# usb2can.net
KiCad netlist of a schematic drawn in EAGLE
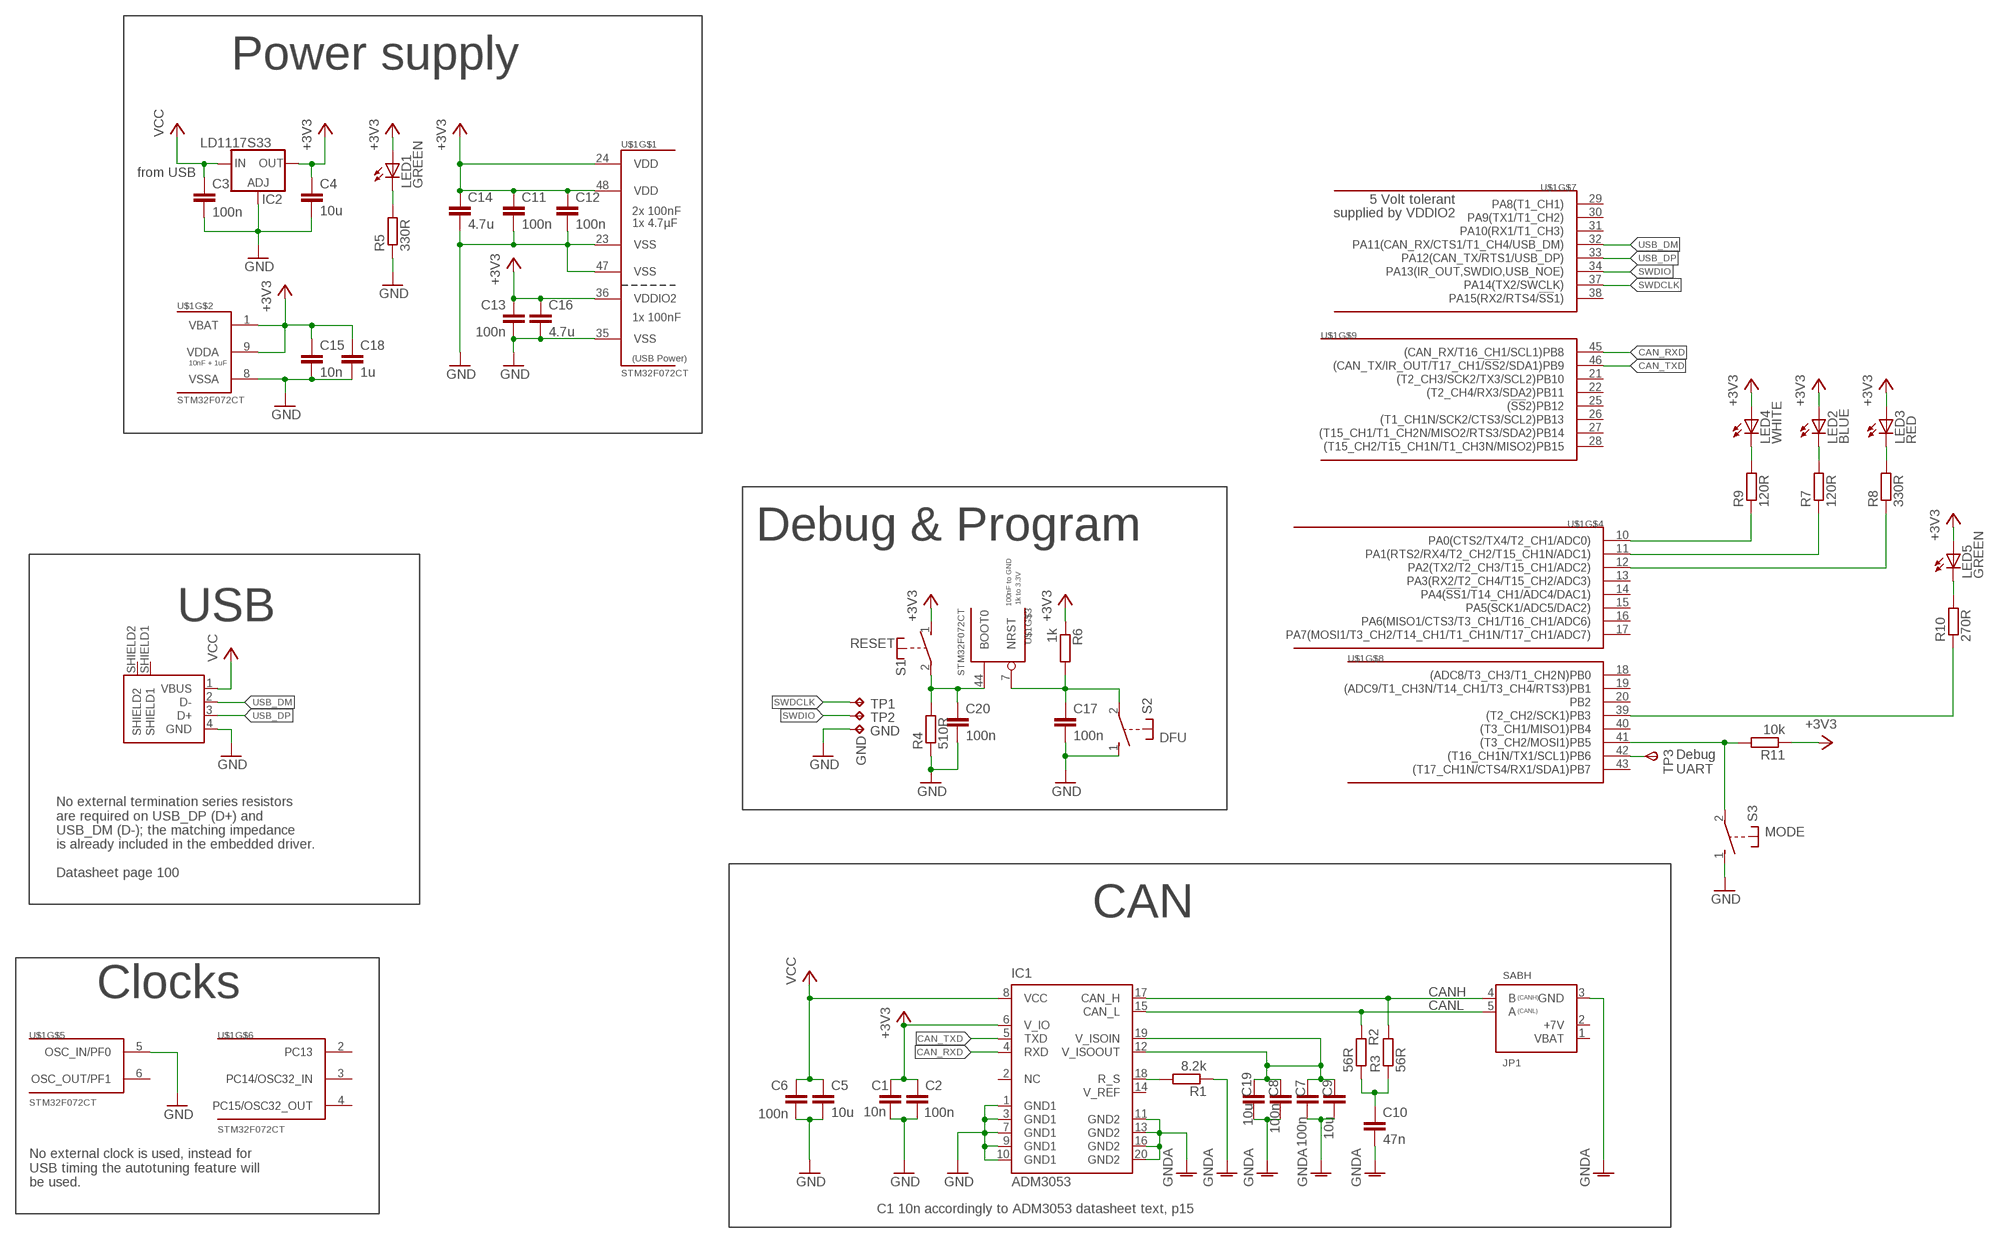
[diagram p0: schematic, sheet 1]

(export (version "E")
  (design (tool "Eeschema 10.0.6"))
  (components
    (comp (ref "C1")
      (value "10n")
      (footprint "eagle-import:C0603K")
      (libsource (lib "eagle-import") (part "C-EUC0603K"))
    )
    (comp (ref "C2")
      (value "100n")
      (footprint "eagle-import:C0603K")
      (libsource (lib "eagle-import") (part "C-EUC0603K"))
    )
    (comp (ref "C3")
      (value "100n")
      (footprint "eagle-import:C0603K")
      (libsource (lib "eagle-import") (part "C-EUC0603K"))
    )
    (comp (ref "C4")
      (value "10u")
      (footprint "eagle-import:C0805K")
      (libsource (lib "eagle-import") (part "C-EUC0805K"))
    )
    (comp (ref "C5")
      (value "10u")
      (footprint "eagle-import:C0805K")
      (libsource (lib "eagle-import") (part "C-EUC0805K"))
    )
    (comp (ref "C6")
      (value "100n")
      (footprint "eagle-import:C0603K")
      (libsource (lib "eagle-import") (part "C-EUC0603K"))
    )
    (comp (ref "C7")
      (value "100n")
      (footprint "eagle-import:C0805K")
      (libsource (lib "eagle-import") (part "C-EUC0805K"))
    )
    (comp (ref "C8")
      (value "100n")
      (footprint "eagle-import:C0805K")
      (libsource (lib "eagle-import") (part "C-EUC0805K"))
    )
    (comp (ref "C9")
      (value "10u")
      (footprint "eagle-import:C0805K")
      (libsource (lib "eagle-import") (part "C-EUC0805K"))
    )
    (comp (ref "C10")
      (value "47n")
      (footprint "eagle-import:C0603K")
      (libsource (lib "eagle-import") (part "C-EUC0603K"))
    )
    (comp (ref "C11")
      (value "100n")
      (footprint "eagle-import:C0603")
      (libsource (lib "eagle-import") (part "C-EUC0603"))
    )
    (comp (ref "C12")
      (value "100n")
      (footprint "eagle-import:C0603")
      (libsource (lib "eagle-import") (part "C-EUC0603"))
    )
    (comp (ref "C13")
      (value "100n")
      (footprint "eagle-import:C0603")
      (libsource (lib "eagle-import") (part "C-EUC0603"))
    )
    (comp (ref "C14")
      (value "4.7u")
      (footprint "eagle-import:C0805K")
      (libsource (lib "eagle-import") (part "C-EUC0805K"))
    )
    (comp (ref "C15")
      (value "10n")
      (footprint "eagle-import:C0603")
      (libsource (lib "eagle-import") (part "C-EUC0603"))
    )
    (comp (ref "C16")
      (value "4.7u")
      (footprint "eagle-import:C0805K")
      (libsource (lib "eagle-import") (part "C-EUC0805K"))
    )
    (comp (ref "C17")
      (value "100n")
      (footprint "eagle-import:C0603")
      (libsource (lib "eagle-import") (part "C-EUC0603"))
    )
    (comp (ref "C18")
      (value "1u")
      (footprint "eagle-import:C0805K")
      (libsource (lib "eagle-import") (part "C-EUC0805K"))
    )
    (comp (ref "C19")
      (value "10u")
      (footprint "eagle-import:C0805K")
      (libsource (lib "eagle-import") (part "C-EUC0805K"))
    )
    (comp (ref "C20")
      (value "100n")
      (footprint "eagle-import:C0603")
      (libsource (lib "eagle-import") (part "C-EUC0603"))
    )
    (comp (ref "CON1")
      (value "USB_A_MALESMD")
      (footprint "eagle-import:USB_A_MALE_SMD")
      (libsource (lib "eagle-import") (part "USB_A_MALESMD"))
    )
    (comp (ref "GND")
      (value "TPB2,54")
      (footprint "eagle-import:B2,54")
      (fields (field (name "TP_SIGNAL_NAME") "GND"))
      (libsource (lib "eagle-import") (part "TPB2,54"))
    )
    (comp (ref "IC1")
      (value "ADM3053")
      (footprint "eagle-import:SO20L")
      (libsource (lib "eagle-import") (part "ADM3053"))
    )
    (comp (ref "IC2")
      (value "LD1117S33")
      (footprint "eagle-import:SOT223")
      (libsource (lib "eagle-import") (part "LD117A?S33TR"))
    )
    (comp (ref "JP1")
      (value "SABH")
      (footprint "eagle-import:7395-05")
      (libsource (lib "eagle-import") (part "SABH"))
    )
    (comp (ref "LED1")
      (value "GREEN")
      (footprint "eagle-import:CHIPLED_0603")
      (libsource (lib "eagle-import") (part "LEDCHIPLED_0603"))
    )
    (comp (ref "LED2")
      (value "BLUE")
      (footprint "eagle-import:CHIPLED_0603")
      (libsource (lib "eagle-import") (part "LEDCHIPLED_0603"))
    )
    (comp (ref "LED3")
      (value "RED")
      (footprint "eagle-import:CHIPLED_0603")
      (libsource (lib "eagle-import") (part "LEDCHIPLED_0603"))
    )
    (comp (ref "LED4")
      (value "WHITE")
      (footprint "eagle-import:CHIPLED_0603")
      (libsource (lib "eagle-import") (part "LEDCHIPLED_0603"))
    )
    (comp (ref "LED5")
      (value "GREEN")
      (footprint "eagle-import:CHIPLED_0603")
      (libsource (lib "eagle-import") (part "LEDCHIPLED_0603"))
    )
    (comp (ref "R1")
      (value "8.2k")
      (footprint "eagle-import:R0603")
      (libsource (lib "eagle-import") (part "R-EU_R0603"))
    )
    (comp (ref "R2")
      (value "56R")
      (footprint "eagle-import:R0805")
      (libsource (lib "eagle-import") (part "R-EU_R0805"))
    )
    (comp (ref "R3")
      (value "56R")
      (footprint "eagle-import:R0805")
      (libsource (lib "eagle-import") (part "R-EU_R0805"))
    )
    (comp (ref "R4")
      (value "510R")
      (footprint "eagle-import:R0603")
      (libsource (lib "eagle-import") (part "resistor_R-EU_R0603"))
    )
    (comp (ref "R5")
      (value "330R")
      (footprint "eagle-import:R0603")
      (libsource (lib "eagle-import") (part "resistor_R-EU_R0603"))
    )
    (comp (ref "R6")
      (value "1k")
      (footprint "eagle-import:R0603")
      (libsource (lib "eagle-import") (part "resistor_R-EU_R0603"))
    )
    (comp (ref "R7")
      (value "120R")
      (footprint "eagle-import:R0603")
      (libsource (lib "eagle-import") (part "resistor_R-EU_R0603"))
    )
    (comp (ref "R8")
      (value "330R")
      (footprint "eagle-import:R0603")
      (libsource (lib "eagle-import") (part "resistor_R-EU_R0603"))
    )
    (comp (ref "R9")
      (value "120R")
      (footprint "eagle-import:R0603")
      (libsource (lib "eagle-import") (part "resistor_R-EU_R0603"))
    )
    (comp (ref "R10")
      (value "270R")
      (footprint "eagle-import:R0603")
      (libsource (lib "eagle-import") (part "resistor_R-EU_R0603"))
    )
    (comp (ref "R11")
      (value "10k")
      (footprint "eagle-import:R0603")
      (libsource (lib "eagle-import") (part "resistor_R-EU_R0603"))
    )
    (comp (ref "S1")
      (value "MICRO_SWITCH_3X6X2.5S")
      (footprint "eagle-import:MICRO_SWITCH_3X6X2.5")
      (libsource (lib "eagle-import") (part "MICRO_SWITCH_3X6X2.5S"))
    )
    (comp (ref "S2")
      (value "MICRO_SWITCH_3X6X2.5S")
      (footprint "eagle-import:MICRO_SWITCH_3X6X2.5")
      (libsource (lib "eagle-import") (part "MICRO_SWITCH_3X6X2.5S"))
    )
    (comp (ref "S3")
      (value "MICRO_SWITCH_3X6X2.5S")
      (footprint "eagle-import:MICRO_SWITCH_3X6X2.5")
      (libsource (lib "eagle-import") (part "MICRO_SWITCH_3X6X2.5S"))
    )
    (comp (ref "TP1")
      (value "TPB2,54")
      (footprint "eagle-import:B2,54")
      (libsource (lib "eagle-import") (part "TPB2,54"))
    )
    (comp (ref "TP2")
      (value "TPB2,54")
      (footprint "eagle-import:B2,54")
      (libsource (lib "eagle-import") (part "TPB2,54"))
    )
    (comp (ref "TP3")
      (value "TPSTP07R")
      (footprint "eagle-import:TP07R")
      (libsource (lib "eagle-import") (part "TPSTP07R"))
    )
    (comp (ref "U$1")
      (value "STM32F072CT")
      (footprint "eagle-import:TQFP48")
      (libsource (lib "eagle-import") (part "STM32F072CT"))
    )
  )
  (nets
    (net (code "1") (name "+3V3") (class "Default")
      (node (ref "C1") (pin "1") (pinfunction "1_1") (pintype "passive"))
      (node (ref "C11") (pin "1") (pinfunction "1_1") (pintype "passive"))
      (node (ref "C12") (pin "1") (pinfunction "1_1") (pintype "passive"))
      (node (ref "C13") (pin "1") (pinfunction "1_1") (pintype "passive"))
      (node (ref "C14") (pin "1") (pinfunction "1_1") (pintype "passive"))
      (node (ref "C15") (pin "1") (pinfunction "1_1") (pintype "passive"))
      (node (ref "C16") (pin "1") (pinfunction "1_1") (pintype "passive"))
      (node (ref "C18") (pin "1") (pinfunction "1_1") (pintype "passive"))
      (node (ref "C2") (pin "1") (pinfunction "1_1") (pintype "passive"))
      (node (ref "C4") (pin "1") (pinfunction "1_1") (pintype "passive"))
      (node (ref "IC1") (pin "6") (pinfunction "V_IO_6") (pintype "power_in"))
      (node (ref "IC2") (pin "4") (pinfunction "OUT_4") (pintype "passive"))
      (node (ref "LED1") (pin "A") (pinfunction "A_A") (pintype "passive"))
      (node (ref "LED2") (pin "A") (pinfunction "A_A") (pintype "passive"))
      (node (ref "LED3") (pin "A") (pinfunction "A_A") (pintype "passive"))
      (node (ref "LED4") (pin "A") (pinfunction "A_A") (pintype "passive"))
      (node (ref "LED5") (pin "A") (pinfunction "A_A") (pintype "passive"))
      (node (ref "R11") (pin "1") (pinfunction "1_1") (pintype "passive"))
      (node (ref "R6") (pin "1") (pinfunction "1_1") (pintype "passive"))
      (node (ref "S1") (pin "1") (pinfunction "1_1") (pintype "passive"))
      (node (ref "U$1") (pin "1") (pinfunction "VBAT_1") (pintype "power_in"))
      (node (ref "U$1") (pin "24") (pinfunction "VDD_24") (pintype "power_in"))
      (node (ref "U$1") (pin "36") (pinfunction "VDDIO2_36") (pintype "power_in"))
      (node (ref "U$1") (pin "48") (pinfunction "VDD_48") (pintype "power_in"))
      (node (ref "U$1") (pin "9") (pinfunction "VDDA_9") (pintype "power_in"))
    )
    (net (code "2") (name "/CANH") (class "Default")
      (node (ref "IC1") (pin "17") (pinfunction "CAN_H_17") (pintype "bidirectional"))
      (node (ref "JP1") (pin "4") (pinfunction "B_4") (pintype "bidirectional"))
      (node (ref "R3") (pin "2") (pinfunction "2_2") (pintype "passive"))
    )
    (net (code "3") (name "/CANL") (class "Default")
      (node (ref "IC1") (pin "15") (pinfunction "CAN_L_15") (pintype "bidirectional"))
      (node (ref "JP1") (pin "5") (pinfunction "A_5") (pintype "bidirectional"))
      (node (ref "R2") (pin "2") (pinfunction "2_2") (pintype "passive"))
    )
    (net (code "4") (name "CAN_RXD") (class "Default")
      (node (ref "IC1") (pin "4") (pinfunction "RXD_4") (pintype "output"))
      (node (ref "U$1") (pin "45") (pinfunction "(CAN_RX/T16_CH1/SCL1)PB8_45") (pintype "bidirectional"))
    )
    (net (code "5") (name "CAN_TXD") (class "Default")
      (node (ref "IC1") (pin "5") (pinfunction "TXD_5") (pintype "input"))
      (node (ref "U$1") (pin "46") (pinfunction "(CAN_TX/IR_OUT/T17_CH1/~{SS}2/SDA1)PB9_46") (pintype "bidirectional"))
    )
    (net (code "6") (name "GND") (class "Default")
      (node (ref "C1") (pin "2") (pinfunction "2_2") (pintype "passive"))
      (node (ref "C11") (pin "2") (pinfunction "2_2") (pintype "passive"))
      (node (ref "C12") (pin "2") (pinfunction "2_2") (pintype "passive"))
      (node (ref "C13") (pin "2") (pinfunction "2_2") (pintype "passive"))
      (node (ref "C14") (pin "2") (pinfunction "2_2") (pintype "passive"))
      (node (ref "C15") (pin "2") (pinfunction "2_2") (pintype "passive"))
      (node (ref "C16") (pin "2") (pinfunction "2_2") (pintype "passive"))
      (node (ref "C17") (pin "2") (pinfunction "2_2") (pintype "passive"))
      (node (ref "C18") (pin "2") (pinfunction "2_2") (pintype "passive"))
      (node (ref "C2") (pin "2") (pinfunction "2_2") (pintype "passive"))
      (node (ref "C20") (pin "2") (pinfunction "2_2") (pintype "passive"))
      (node (ref "C3") (pin "2") (pinfunction "2_2") (pintype "passive"))
      (node (ref "C4") (pin "2") (pinfunction "2_2") (pintype "passive"))
      (node (ref "C5") (pin "2") (pinfunction "2_2") (pintype "passive"))
      (node (ref "C6") (pin "2") (pinfunction "2_2") (pintype "passive"))
      (node (ref "CON1") (pin "4") (pinfunction "GND_4") (pintype "power_in"))
      (node (ref "GND") (pin "TP") (pinfunction "TP_TP") (pintype "input"))
      (node (ref "IC1") (pin "1") (pinfunction "GND1_1") (pintype "power_in"))
      (node (ref "IC1") (pin "10") (pinfunction "GND1_10") (pintype "power_in"))
      (node (ref "IC1") (pin "3") (pinfunction "GND1_3") (pintype "power_in"))
      (node (ref "IC1") (pin "7") (pinfunction "GND1_7") (pintype "power_in"))
      (node (ref "IC1") (pin "9") (pinfunction "GND1_9") (pintype "power_in"))
      (node (ref "IC2") (pin "1") (pinfunction "ADJ_1") (pintype "input"))
      (node (ref "R4") (pin "1") (pinfunction "1_1") (pintype "passive"))
      (node (ref "R5") (pin "1") (pinfunction "1_1") (pintype "passive"))
      (node (ref "S2") (pin "1") (pinfunction "1_1") (pintype "passive"))
      (node (ref "S3") (pin "1") (pinfunction "1_1") (pintype "passive"))
      (node (ref "U$1") (pin "23") (pinfunction "VSS_23") (pintype "power_in"))
      (node (ref "U$1") (pin "35") (pinfunction "VSS_35") (pintype "power_in"))
      (node (ref "U$1") (pin "47") (pinfunction "VSS_47") (pintype "power_in"))
      (node (ref "U$1") (pin "5") (pinfunction "OSC_IN/PF0_5") (pintype "input"))
      (node (ref "U$1") (pin "8") (pinfunction "VSSA_8") (pintype "power_in"))
    )
    (net (code "7") (name "GNDA") (class "Default")
      (node (ref "C10") (pin "2") (pinfunction "2_2") (pintype "passive"))
      (node (ref "C19") (pin "2") (pinfunction "2_2") (pintype "passive"))
      (node (ref "C7") (pin "2") (pinfunction "2_2") (pintype "passive"))
      (node (ref "C8") (pin "2") (pinfunction "2_2") (pintype "passive"))
      (node (ref "C9") (pin "2") (pinfunction "2_2") (pintype "passive"))
      (node (ref "IC1") (pin "11") (pinfunction "GND2_11") (pintype "power_in"))
      (node (ref "IC1") (pin "13") (pinfunction "GND2_13") (pintype "power_in"))
      (node (ref "IC1") (pin "16") (pinfunction "GND2_16") (pintype "power_in"))
      (node (ref "IC1") (pin "20") (pinfunction "GND2_20") (pintype "power_in"))
      (node (ref "JP1") (pin "3") (pinfunction "GND_3") (pintype "power_in"))
      (node (ref "R1") (pin "1") (pinfunction "1_1") (pintype "passive"))
    )
    (net (code "8") (name "Net-(C10-Pad1)") (class "Default")
      (node (ref "C10") (pin "1") (pinfunction "1_1") (pintype "passive"))
      (node (ref "R2") (pin "1") (pinfunction "1_1") (pintype "passive"))
      (node (ref "R3") (pin "1") (pinfunction "1_1") (pintype "passive"))
    )
    (net (code "9") (name "Net-(IC1-R_S)") (class "Default")
      (node (ref "IC1") (pin "18") (pinfunction "R_S_18") (pintype "passive"))
      (node (ref "R1") (pin "2") (pinfunction "2_2") (pintype "passive"))
    )
    (net (code "10") (name "Net-(IC1-V_ISOIN)") (class "Default")
      (node (ref "C19") (pin "1") (pinfunction "1_1") (pintype "passive"))
      (node (ref "C7") (pin "1") (pinfunction "1_1") (pintype "passive"))
      (node (ref "C8") (pin "1") (pinfunction "1_1") (pintype "passive"))
      (node (ref "C9") (pin "1") (pinfunction "1_1") (pintype "passive"))
      (node (ref "IC1") (pin "12") (pinfunction "V_ISOOUT_12") (pintype "output"))
      (node (ref "IC1") (pin "19") (pinfunction "V_ISOIN_19") (pintype "input"))
    )
    (net (code "11") (name "Net-(LED1-PadC)") (class "Default")
      (node (ref "LED1") (pin "C") (pinfunction "C_C") (pintype "passive"))
      (node (ref "R5") (pin "2") (pinfunction "2_2") (pintype "passive"))
    )
    (net (code "12") (name "Net-(LED2-PadC)") (class "Default")
      (node (ref "LED2") (pin "C") (pinfunction "C_C") (pintype "passive"))
      (node (ref "R7") (pin "2") (pinfunction "2_2") (pintype "passive"))
    )
    (net (code "13") (name "Net-(LED3-PadC)") (class "Default")
      (node (ref "LED3") (pin "C") (pinfunction "C_C") (pintype "passive"))
      (node (ref "R8") (pin "2") (pinfunction "2_2") (pintype "passive"))
    )
    (net (code "14") (name "Net-(LED4-PadC)") (class "Default")
      (node (ref "LED4") (pin "C") (pinfunction "C_C") (pintype "passive"))
      (node (ref "R9") (pin "2") (pinfunction "2_2") (pintype "passive"))
    )
    (net (code "15") (name "Net-(LED5-PadC)") (class "Default")
      (node (ref "LED5") (pin "C") (pinfunction "C_C") (pintype "passive"))
      (node (ref "R10") (pin "2") (pinfunction "2_2") (pintype "passive"))
    )
    (net (code "16") (name "Net-(TP3-PP)") (class "Default")
      (node (ref "TP3") (pin "TP") (pinfunction "PP_TP") (pintype "input"))
      (node (ref "U$1") (pin "42") (pinfunction "(T16_CH1N/TX1/SCL1)PB6_42") (pintype "bidirectional"))
    )
    (net (code "17") (name "Net-(U$1C-BOOT0)") (class "Default")
      (node (ref "C20") (pin "1") (pinfunction "1_1") (pintype "passive"))
      (node (ref "R4") (pin "2") (pinfunction "2_2") (pintype "passive"))
      (node (ref "S1") (pin "2") (pinfunction "2_2") (pintype "passive"))
      (node (ref "U$1") (pin "44") (pinfunction "BOOT0_44") (pintype "input"))
    )
    (net (code "18") (name "Net-(U$1C-NRST)") (class "Default")
      (node (ref "C17") (pin "1") (pinfunction "1_1") (pintype "passive"))
      (node (ref "R6") (pin "2") (pinfunction "2_2") (pintype "passive"))
      (node (ref "S2") (pin "2") (pinfunction "2_2") (pintype "passive"))
      (node (ref "U$1") (pin "7") (pinfunction "NRST_7") (pintype "input"))
    )
    (net (code "19") (name "Net-(U$1D-PA0(CTS2{slash}TX4{slash}T2_CH1{slash}ADC0))") (class "Default")
      (node (ref "R9") (pin "1") (pinfunction "1_1") (pintype "passive"))
      (node (ref "U$1") (pin "10") (pinfunction "PA0(CTS2/TX4/T2_CH1/ADC0)_10") (pintype "bidirectional"))
    )
    (net (code "20") (name "Net-(U$1D-PA1(RTS2{slash}RX4{slash}T2_CH2{slash}T15_CH1N{slash}ADC1))") (class "Default")
      (node (ref "R7") (pin "1") (pinfunction "1_1") (pintype "passive"))
      (node (ref "U$1") (pin "11") (pinfunction "PA1(RTS2/RX4/T2_CH2/T15_CH1N/ADC1)_11") (pintype "bidirectional"))
    )
    (net (code "21") (name "Net-(U$1D-PA2(TX2{slash}T2_CH3{slash}T15_CH1{slash}ADC2))") (class "Default")
      (node (ref "R8") (pin "1") (pinfunction "1_1") (pintype "passive"))
      (node (ref "U$1") (pin "12") (pinfunction "PA2(TX2/T2_CH3/T15_CH1/ADC2)_12") (pintype "bidirectional"))
    )
    (net (code "22") (name "Net-(U$1H-(T2_CH2{slash}SCK1)PB3)") (class "Default")
      (node (ref "R10") (pin "1") (pinfunction "1_1") (pintype "passive"))
      (node (ref "U$1") (pin "39") (pinfunction "(T2_CH2/SCK1)PB3_39") (pintype "bidirectional"))
    )
    (net (code "23") (name "Net-(U$1H-(T3_CH2{slash}MOSI1)PB5)") (class "Default")
      (node (ref "R11") (pin "2") (pinfunction "2_2") (pintype "passive"))
      (node (ref "S3") (pin "2") (pinfunction "2_2") (pintype "passive"))
      (node (ref "U$1") (pin "41") (pinfunction "(T3_CH2/MOSI1)PB5_41") (pintype "bidirectional"))
    )
    (net (code "24") (name "SWDCLK") (class "Default")
      (node (ref "TP1") (pin "TP") (pinfunction "TP_TP") (pintype "input"))
      (node (ref "U$1") (pin "37") (pinfunction "PA14(TX2/SWCLK)_37") (pintype "bidirectional"))
    )
    (net (code "25") (name "SWDIO") (class "Default")
      (node (ref "TP2") (pin "TP") (pinfunction "TP_TP") (pintype "input"))
      (node (ref "U$1") (pin "34") (pinfunction "PA13(IR_OUT,SWDIO,USB_NOE)_34") (pintype "bidirectional"))
    )
    (net (code "26") (name "USB_DM") (class "Default")
      (node (ref "CON1") (pin "2") (pinfunction "D-_2") (pintype "bidirectional"))
      (node (ref "U$1") (pin "32") (pinfunction "PA11(CAN_RX/CTS1/T1_CH4/USB_DM)_32") (pintype "bidirectional"))
    )
    (net (code "27") (name "USB_DP") (class "Default")
      (node (ref "CON1") (pin "3") (pinfunction "D+_3") (pintype "bidirectional"))
      (node (ref "U$1") (pin "33") (pinfunction "PA12(CAN_TX/RTS1/USB_DP)_33") (pintype "bidirectional"))
    )
    (net (code "28") (name "VCC") (class "Default")
      (node (ref "C3") (pin "1") (pinfunction "1_1") (pintype "passive"))
      (node (ref "C5") (pin "1") (pinfunction "1_1") (pintype "passive"))
      (node (ref "C6") (pin "1") (pinfunction "1_1") (pintype "passive"))
      (node (ref "CON1") (pin "1") (pinfunction "VBUS_1") (pintype "power_in"))
      (node (ref "IC1") (pin "8") (pinfunction "VCC_8") (pintype "power_in"))
      (node (ref "IC2") (pin "3") (pinfunction "IN_3") (pintype "input"))
    )
    (net (code "29") (name "unconnected-(CON1-PadSHIELD1)") (class "Default")
      (node (ref "CON1") (pin "SHIELD1") (pinfunction "SHIELD1_SHIELD1") (pintype "passive"))
    )
    (net (code "30") (name "unconnected-(CON1-PadSHIELD2)") (class "Default")
      (node (ref "CON1") (pin "SHIELD2") (pinfunction "SHIELD2_SHIELD2") (pintype "passive"))
    )
    (net (code "31") (name "unconnected-(IC1-NC-Pad2)") (class "Default")
      (node (ref "IC1") (pin "2") (pinfunction "NC_2") (pintype "no_connect"))
    )
    (net (code "32") (name "unconnected-(IC1-V_REF-Pad14)") (class "Default")
      (node (ref "IC1") (pin "14") (pinfunction "V_REF_14") (pintype "output"))
    )
    (net (code "33") (name "unconnected-(JP1-+7V-Pad2)") (class "Default")
      (node (ref "JP1") (pin "2") (pinfunction "+7V_2") (pintype "no_connect"))
    )
    (net (code "34") (name "unconnected-(JP1-VBAT-Pad1)") (class "Default")
      (node (ref "JP1") (pin "1") (pinfunction "VBAT_1") (pintype "no_connect"))
    )
    (net (code "35") (name "unconnected-(U$1D-PA3(RX2{slash}T2_CH4{slash}T15_CH2{slash}ADC3)-Pad13)") (class "Default")
      (node (ref "U$1") (pin "13") (pinfunction "PA3(RX2/T2_CH4/T15_CH2/ADC3)_13") (pintype "bidirectional"))
    )
    (net (code "36") (name "unconnected-(U$1D-PA4(~{SS}1{slash}T14_CH1{slash}ADC4{slash}DAC1)-Pad14)") (class "Default")
      (node (ref "U$1") (pin "14") (pinfunction "PA4(~{SS}1/T14_CH1/ADC4/DAC1)_14") (pintype "bidirectional"))
    )
    (net (code "37") (name "unconnected-(U$1D-PA5(SCK1{slash}ADC5{slash}DAC2)-Pad15)") (class "Default")
      (node (ref "U$1") (pin "15") (pinfunction "PA5(SCK1/ADC5/DAC2)_15") (pintype "bidirectional"))
    )
    (net (code "38") (name "unconnected-(U$1D-PA6(MISO1{slash}CTS3{slash}T3_CH1{slash}T16_CH1{slash}ADC6)-Pad16)") (class "Default")
      (node (ref "U$1") (pin "16") (pinfunction "PA6(MISO1/CTS3/T3_CH1/T16_CH1/ADC6)_16") (pintype "bidirectional"))
    )
    (net (code "39") (name "unconnected-(U$1D-PA7(MOSI1{slash}T3_CH2{slash}T14_CH1{slash}T1_CH1N{slash}T17_CH1{slash}ADC7)-Pad17)") (class "Default")
      (node (ref "U$1") (pin "17") (pinfunction "PA7(MOSI1/T3_CH2/T14_CH1/T1_CH1N/T17_CH1/ADC7)_17") (pintype "bidirectional"))
    )
    (net (code "40") (name "unconnected-(U$1E-OSC_OUT{slash}PF1-Pad6)") (class "Default")
      (node (ref "U$1") (pin "6") (pinfunction "OSC_OUT/PF1_6") (pintype "output"))
    )
    (net (code "41") (name "unconnected-(U$1F-PC13-Pad2)") (class "Default")
      (node (ref "U$1") (pin "2") (pinfunction "PC13_2") (pintype "bidirectional"))
    )
    (net (code "42") (name "unconnected-(U$1F-PC14{slash}OSC32_IN-Pad3)") (class "Default")
      (node (ref "U$1") (pin "3") (pinfunction "PC14/OSC32_IN_3") (pintype "bidirectional"))
    )
    (net (code "43") (name "unconnected-(U$1F-PC15{slash}OSC32_OUT-Pad4)") (class "Default")
      (node (ref "U$1") (pin "4") (pinfunction "PC15/OSC32_OUT_4") (pintype "bidirectional"))
    )
    (net (code "44") (name "unconnected-(U$1G-PA8(T1_CH1)-Pad29)") (class "Default")
      (node (ref "U$1") (pin "29") (pinfunction "PA8(T1_CH1)_29") (pintype "bidirectional"))
    )
    (net (code "45") (name "unconnected-(U$1G-PA9(TX1{slash}T1_CH2)-Pad30)") (class "Default")
      (node (ref "U$1") (pin "30") (pinfunction "PA9(TX1/T1_CH2)_30") (pintype "bidirectional"))
    )
    (net (code "46") (name "unconnected-(U$1G-PA10(RX1{slash}T1_CH3)-Pad31)") (class "Default")
      (node (ref "U$1") (pin "31") (pinfunction "PA10(RX1/T1_CH3)_31") (pintype "bidirectional"))
    )
    (net (code "47") (name "unconnected-(U$1G-PA15(RX2{slash}RTS4{slash}~{SS}1)-Pad38)") (class "Default")
      (node (ref "U$1") (pin "38") (pinfunction "PA15(RX2/RTS4/~{SS}1)_38") (pintype "bidirectional"))
    )
    (net (code "48") (name "unconnected-(U$1H-(ADC8{slash}T3_CH3{slash}T1_CH2N)PB0-Pad18)") (class "Default")
      (node (ref "U$1") (pin "18") (pinfunction "(ADC8/T3_CH3/T1_CH2N)PB0_18") (pintype "bidirectional"))
    )
    (net (code "49") (name "unconnected-(U$1H-(ADC9{slash}T1_CH3N{slash}T14_CH1{slash}T3_CH4{slash}RTS3)PB1-Pad19)") (class "Default")
      (node (ref "U$1") (pin "19") (pinfunction "(ADC9/T1_CH3N/T14_CH1/T3_CH4/RTS3)PB1_19") (pintype "bidirectional"))
    )
    (net (code "50") (name "unconnected-(U$1H-(T3_CH1{slash}MISO1)PB4-Pad40)") (class "Default")
      (node (ref "U$1") (pin "40") (pinfunction "(T3_CH1/MISO1)PB4_40") (pintype "bidirectional"))
    )
    (net (code "51") (name "unconnected-(U$1H-(T17_CH1N{slash}CTS4{slash}RX1{slash}SDA1)PB7-Pad43)") (class "Default")
      (node (ref "U$1") (pin "43") (pinfunction "(T17_CH1N/CTS4/RX1/SDA1)PB7_43") (pintype "bidirectional"))
    )
    (net (code "52") (name "unconnected-(U$1H-PB2-Pad20)") (class "Default")
      (node (ref "U$1") (pin "20") (pinfunction "PB2_20") (pintype "bidirectional"))
    )
    (net (code "53") (name "unconnected-(U$1I-(T1_CH1N{slash}SCK2{slash}CTS3{slash}SCL2)PB13-Pad26)") (class "Default")
      (node (ref "U$1") (pin "26") (pinfunction "(T1_CH1N/SCK2/CTS3/SCL2)PB13_26") (pintype "bidirectional"))
    )
    (net (code "54") (name "unconnected-(U$1I-(T2_CH3{slash}SCK2{slash}TX3{slash}SCL2)PB10-Pad21)") (class "Default")
      (node (ref "U$1") (pin "21") (pinfunction "(T2_CH3/SCK2/TX3/SCL2)PB10_21") (pintype "bidirectional"))
    )
    (net (code "55") (name "unconnected-(U$1I-(T2_CH4{slash}RX3{slash}SDA2)PB11-Pad22)") (class "Default")
      (node (ref "U$1") (pin "22") (pinfunction "(T2_CH4/RX3/SDA2)PB11_22") (pintype "bidirectional"))
    )
    (net (code "56") (name "unconnected-(U$1I-(T15_CH1{slash}T1_CH2N{slash}MISO2{slash}RTS3{slash}SDA2)PB14-Pad27)") (class "Default")
      (node (ref "U$1") (pin "27") (pinfunction "(T15_CH1/T1_CH2N/MISO2/RTS3/SDA2)PB14_27") (pintype "bidirectional"))
    )
    (net (code "57") (name "unconnected-(U$1I-(T15_CH2{slash}T15_CH1N{slash}T1_CH3N{slash}MISO2)PB15-Pad28)") (class "Default")
      (node (ref "U$1") (pin "28") (pinfunction "(T15_CH2/T15_CH1N/T1_CH3N/MISO2)PB15_28") (pintype "bidirectional"))
    )
    (net (code "58") (name "unconnected-(U$1I-(~{SS}2)PB12-Pad25)") (class "Default")
      (node (ref "U$1") (pin "25") (pinfunction "(~{SS}2)PB12_25") (pintype "bidirectional"))
    )
  )
)
